# YUSynth-LFO-mainboard.net
KiCad netlist of a schematic drawn in EAGLE
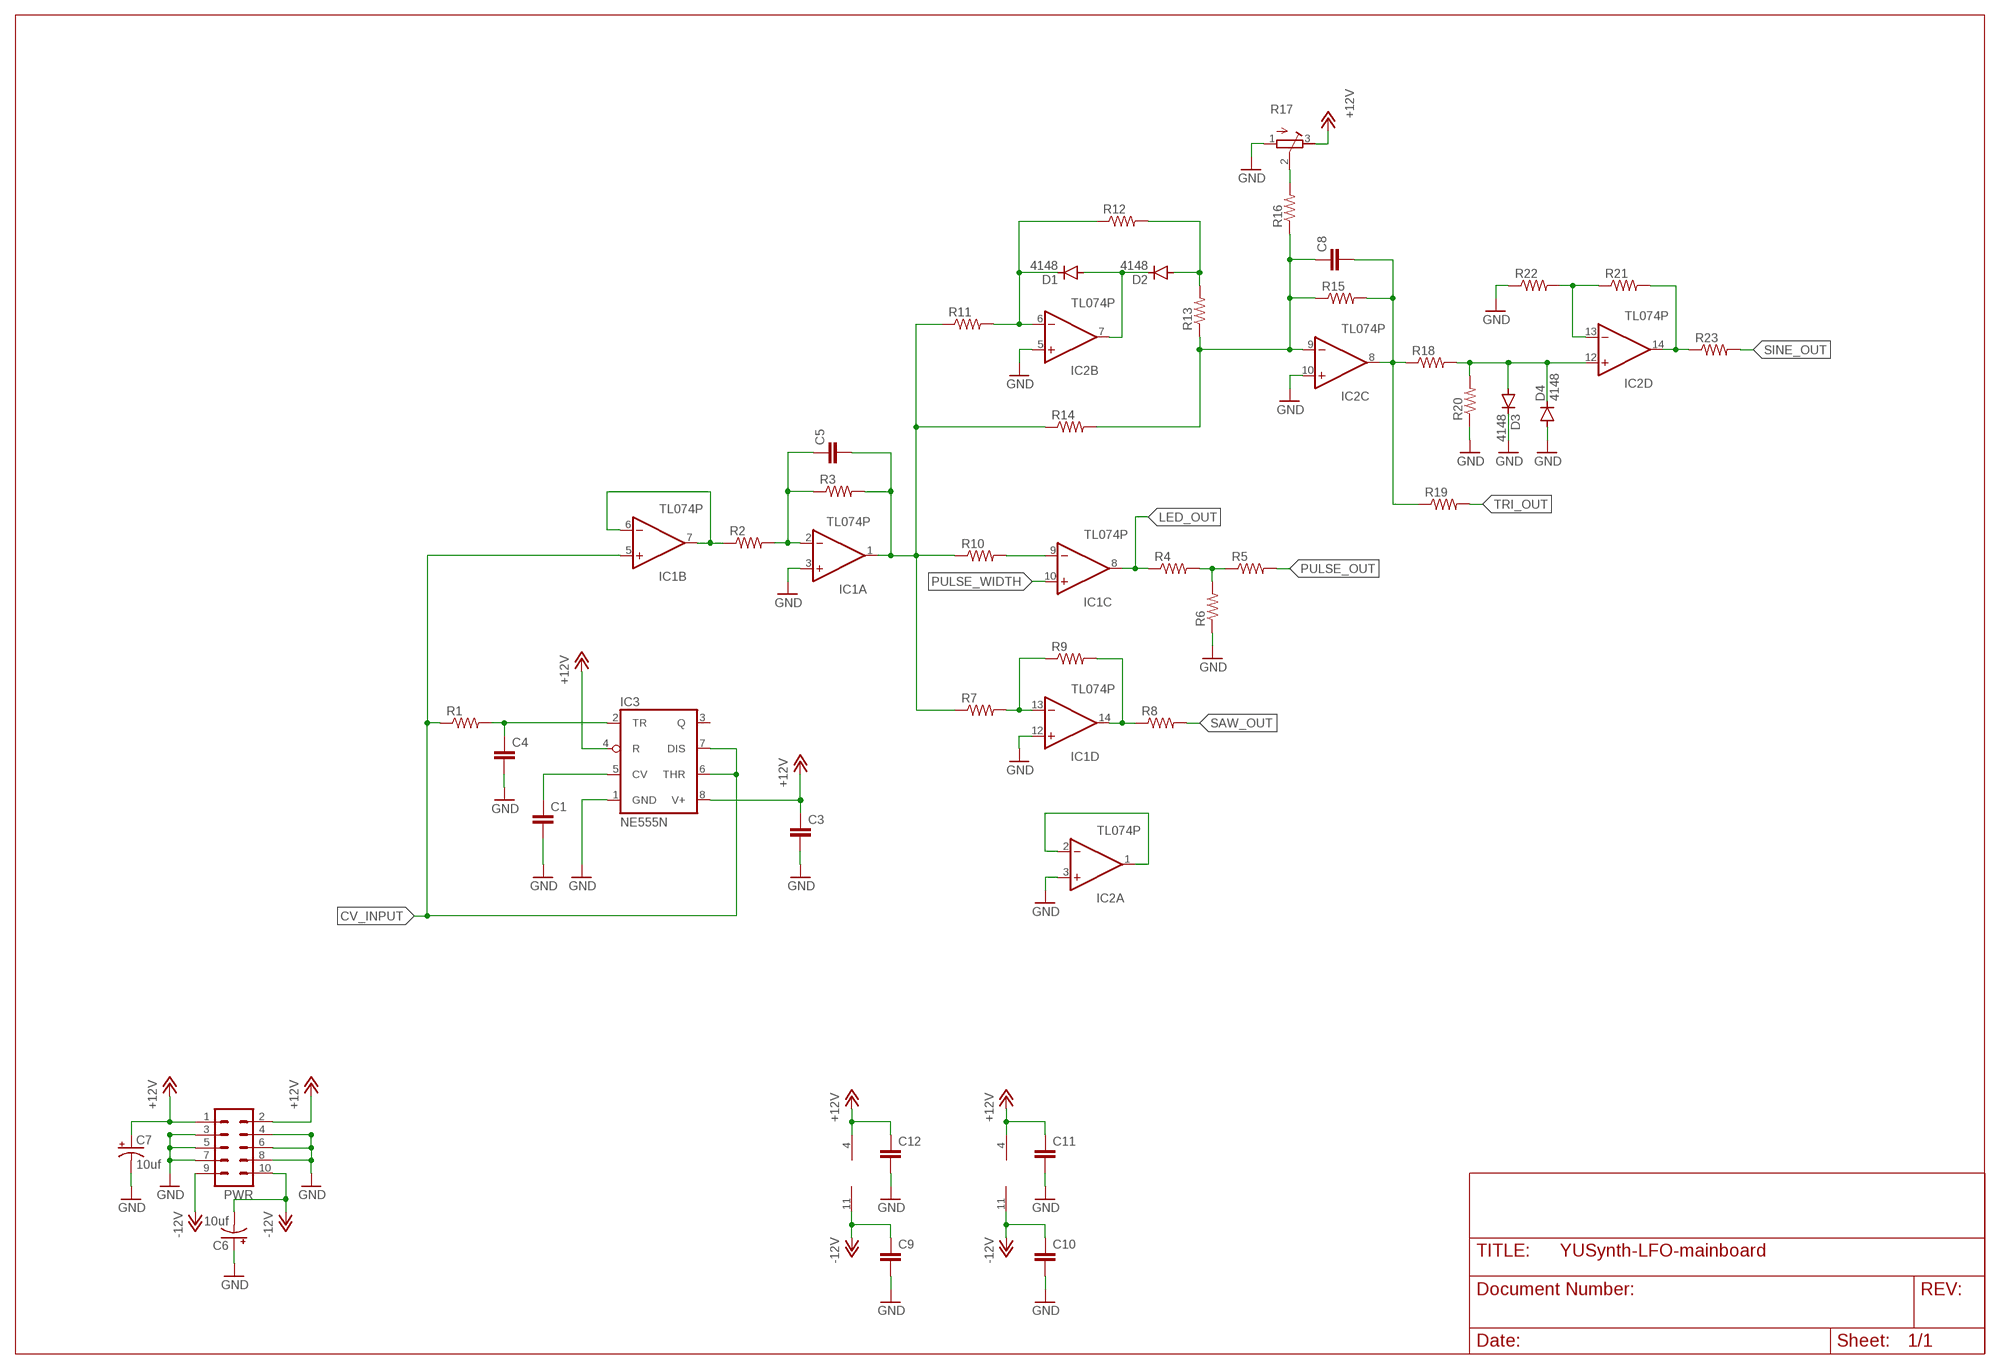
[diagram p0: schematic, sheet 1]

(export (version "E")
  (design (tool "Eeschema 10.0.6"))
  (components
    (comp (ref "C1")
      (value "C-EU050-024X044")
      (footprint "eagle-import:C050-024X044")
      (libsource (lib "eagle-import") (part "C-EU050-024X044"))
    )
    (comp (ref "C3")
      (value "C-EU050-024X044")
      (footprint "eagle-import:C050-024X044")
      (libsource (lib "eagle-import") (part "C-EU050-024X044"))
    )
    (comp (ref "C4")
      (value "C-EU050-024X044")
      (footprint "eagle-import:C050-024X044")
      (libsource (lib "eagle-import") (part "C-EU050-024X044"))
    )
    (comp (ref "C5")
      (value "C-EU050-024X044")
      (footprint "eagle-import:C050-024X044")
      (libsource (lib "eagle-import") (part "C-EU050-024X044"))
    )
    (comp (ref "C6")
      (value "10uf")
      (footprint "eagle-import:E2,5-5")
      (libsource (lib "eagle-import") (part "CPOL-USE2.5-5"))
    )
    (comp (ref "C7")
      (value "10uf")
      (footprint "eagle-import:E2,5-5")
      (libsource (lib "eagle-import") (part "CPOL-USE2.5-5"))
    )
    (comp (ref "C8")
      (value "C-EU050-024X044")
      (footprint "eagle-import:C050-024X044")
      (libsource (lib "eagle-import") (part "C-EU050-024X044"))
    )
    (comp (ref "C9")
      (value "C-EU050-024X044")
      (footprint "eagle-import:C050-024X044")
      (libsource (lib "eagle-import") (part "C-EU050-024X044"))
    )
    (comp (ref "C10")
      (value "C-EU050-024X044")
      (footprint "eagle-import:C050-024X044")
      (libsource (lib "eagle-import") (part "C-EU050-024X044"))
    )
    (comp (ref "C11")
      (value "C-EU050-024X044")
      (footprint "eagle-import:C050-024X044")
      (libsource (lib "eagle-import") (part "C-EU050-024X044"))
    )
    (comp (ref "C12")
      (value "C-EU050-024X044")
      (footprint "eagle-import:C050-024X044")
      (libsource (lib "eagle-import") (part "C-EU050-024X044"))
    )
    (comp (ref "D1")
      (value "4148")
      (footprint "eagle-import:DO35-7")
      (libsource (lib "eagle-import") (part "1N4148DO35-7"))
    )
    (comp (ref "D2")
      (value "4148")
      (footprint "eagle-import:DO35-7")
      (libsource (lib "eagle-import") (part "1N4148DO35-7"))
    )
    (comp (ref "D3")
      (value "4148")
      (footprint "eagle-import:DO35-7")
      (libsource (lib "eagle-import") (part "1N4148DO35-7"))
    )
    (comp (ref "D4")
      (value "4148")
      (footprint "eagle-import:DO35-7")
      (libsource (lib "eagle-import") (part "1N4148DO35-7"))
    )
    (comp (ref "IC1")
      (value "TL074P")
      (footprint "eagle-import:DIL14")
      (libsource (lib "eagle-import") (part "TL074P"))
    )
    (comp (ref "IC2")
      (value "TL074P")
      (footprint "eagle-import:DIL14")
      (libsource (lib "eagle-import") (part "TL074P"))
    )
    (comp (ref "IC3")
      (value "NE555N")
      (footprint "eagle-import:DIL08")
      (libsource (lib "eagle-import") (part "555NNE"))
    )
    (comp (ref "PWR")
      (value "ML10")
      (footprint "eagle-import:ML10")
      (libsource (lib "eagle-import") (part "ML10"))
    )
    (comp (ref "R1")
      (value "R-US_0207/7")
      (footprint "eagle-import:0207_7")
      (libsource (lib "eagle-import") (part "R-US_0207/7"))
    )
    (comp (ref "R2")
      (value "R-US_0207/7")
      (footprint "eagle-import:0207_7")
      (libsource (lib "eagle-import") (part "R-US_0207/7"))
    )
    (comp (ref "R3")
      (value "R-US_0207/7")
      (footprint "eagle-import:0207_7")
      (libsource (lib "eagle-import") (part "R-US_0207/7"))
    )
    (comp (ref "R4")
      (value "R-US_0207/7")
      (footprint "eagle-import:0207_7")
      (libsource (lib "eagle-import") (part "R-US_0207/7"))
    )
    (comp (ref "R5")
      (value "R-US_0207/7")
      (footprint "eagle-import:0207_7")
      (libsource (lib "eagle-import") (part "R-US_0207/7"))
    )
    (comp (ref "R6")
      (value "R-US_0207/7")
      (footprint "eagle-import:0207_7")
      (libsource (lib "eagle-import") (part "R-US_0207/7"))
    )
    (comp (ref "R7")
      (value "R-US_0207/7")
      (footprint "eagle-import:0207_7")
      (libsource (lib "eagle-import") (part "R-US_0207/7"))
    )
    (comp (ref "R8")
      (value "R-US_0207/7")
      (footprint "eagle-import:0207_7")
      (libsource (lib "eagle-import") (part "R-US_0207/7"))
    )
    (comp (ref "R9")
      (value "R-US_0207/7")
      (footprint "eagle-import:0207_7")
      (libsource (lib "eagle-import") (part "R-US_0207/7"))
    )
    (comp (ref "R10")
      (value "R-US_0207/7")
      (footprint "eagle-import:0207_7")
      (libsource (lib "eagle-import") (part "R-US_0207/7"))
    )
    (comp (ref "R11")
      (value "R-US_0207/7")
      (footprint "eagle-import:0207_7")
      (libsource (lib "eagle-import") (part "R-US_0207/7"))
    )
    (comp (ref "R12")
      (value "R-US_0207/7")
      (footprint "eagle-import:0207_7")
      (libsource (lib "eagle-import") (part "R-US_0207/7"))
    )
    (comp (ref "R13")
      (value "R-US_0207/7")
      (footprint "eagle-import:0207_7")
      (libsource (lib "eagle-import") (part "R-US_0207/7"))
    )
    (comp (ref "R14")
      (value "R-US_0207/7")
      (footprint "eagle-import:0207_7")
      (libsource (lib "eagle-import") (part "R-US_0207/7"))
    )
    (comp (ref "R15")
      (value "R-US_0207/7")
      (footprint "eagle-import:0207_7")
      (libsource (lib "eagle-import") (part "R-US_0207/7"))
    )
    (comp (ref "R16")
      (value "R-US_0207/7")
      (footprint "eagle-import:0207_7")
      (libsource (lib "eagle-import") (part "R-US_0207/7"))
    )
    (comp (ref "R17")
      (value "R-TRIMM64W")
      (footprint "eagle-import:RTRIM64W")
      (libsource (lib "eagle-import") (part "R-TRIMM64W"))
    )
    (comp (ref "R18")
      (value "R-US_0207/7")
      (footprint "eagle-import:0207_7")
      (libsource (lib "eagle-import") (part "R-US_0207/7"))
    )
    (comp (ref "R19")
      (value "R-US_0207/7")
      (footprint "eagle-import:0207_7")
      (libsource (lib "eagle-import") (part "R-US_0207/7"))
    )
    (comp (ref "R20")
      (value "R-US_0207/7")
      (footprint "eagle-import:0207_7")
      (libsource (lib "eagle-import") (part "R-US_0207/7"))
    )
    (comp (ref "R21")
      (value "R-US_0207/7")
      (footprint "eagle-import:0207_7")
      (libsource (lib "eagle-import") (part "R-US_0207/7"))
    )
    (comp (ref "R22")
      (value "R-US_0207/7")
      (footprint "eagle-import:0207_7")
      (libsource (lib "eagle-import") (part "R-US_0207/7"))
    )
    (comp (ref "R23")
      (value "R-US_0207/7")
      (footprint "eagle-import:0207_7")
      (libsource (lib "eagle-import") (part "R-US_0207/7"))
    )
  )
  (nets
    (net (code "1") (name "+12V") (class "Default")
      (node (ref "C11") (pin "1") (pinfunction "1_1") (pintype "passive"))
      (node (ref "C12") (pin "1") (pinfunction "1_1") (pintype "passive"))
      (node (ref "C3") (pin "1") (pinfunction "1_1") (pintype "passive"))
      (node (ref "C7") (pin "+") (pinfunction "+_+") (pintype "passive"))
      (node (ref "IC1") (pin "4") (pinfunction "V+_4") (pintype "power_in"))
      (node (ref "IC2") (pin "4") (pinfunction "V+_4") (pintype "power_in"))
      (node (ref "IC3") (pin "4") (pinfunction "R_4") (pintype "input"))
      (node (ref "IC3") (pin "8") (pinfunction "V+_8") (pintype "power_in"))
      (node (ref "PWR") (pin "1") (pinfunction "1_1") (pintype "passive"))
      (node (ref "PWR") (pin "2") (pinfunction "2_2") (pintype "passive"))
      (node (ref "R17") (pin "3") (pinfunction "E_3") (pintype "passive"))
    )
    (net (code "2") (name "-12V") (class "Default")
      (node (ref "C10") (pin "1") (pinfunction "1_1") (pintype "passive"))
      (node (ref "C6") (pin "-") (pinfunction "-_-") (pintype "passive"))
      (node (ref "C9") (pin "1") (pinfunction "1_1") (pintype "passive"))
      (node (ref "IC1") (pin "11") (pinfunction "V-_11") (pintype "power_in"))
      (node (ref "IC2") (pin "11") (pinfunction "V-_11") (pintype "power_in"))
      (node (ref "PWR") (pin "10") (pinfunction "10_10") (pintype "passive"))
      (node (ref "PWR") (pin "9") (pinfunction "9_9") (pintype "passive"))
    )
    (net (code "3") (name "CV_INPUT") (class "Default")
      (node (ref "IC1") (pin "5") (pinfunction "+IN_5") (pintype "input"))
      (node (ref "IC3") (pin "6") (pinfunction "THR_6") (pintype "input"))
      (node (ref "IC3") (pin "7") (pinfunction "DIS_7") (pintype "input"))
      (node (ref "R1") (pin "1") (pinfunction "1_1") (pintype "passive"))
    )
    (net (code "4") (name "GND") (class "Default")
      (node (ref "C1") (pin "2") (pinfunction "2_2") (pintype "passive"))
      (node (ref "C10") (pin "2") (pinfunction "2_2") (pintype "passive"))
      (node (ref "C11") (pin "2") (pinfunction "2_2") (pintype "passive"))
      (node (ref "C12") (pin "2") (pinfunction "2_2") (pintype "passive"))
      (node (ref "C3") (pin "2") (pinfunction "2_2") (pintype "passive"))
      (node (ref "C4") (pin "2") (pinfunction "2_2") (pintype "passive"))
      (node (ref "C6") (pin "+") (pinfunction "+_+") (pintype "passive"))
      (node (ref "C7") (pin "-") (pinfunction "-_-") (pintype "passive"))
      (node (ref "C9") (pin "2") (pinfunction "2_2") (pintype "passive"))
      (node (ref "D3") (pin "C") (pinfunction "C_C") (pintype "passive"))
      (node (ref "D4") (pin "A") (pinfunction "A_A") (pintype "passive"))
      (node (ref "IC1") (pin "12") (pinfunction "+IN_12") (pintype "input"))
      (node (ref "IC1") (pin "3") (pinfunction "+IN_3") (pintype "input"))
      (node (ref "IC2") (pin "10") (pinfunction "+IN_10") (pintype "input"))
      (node (ref "IC2") (pin "3") (pinfunction "+IN_3") (pintype "input"))
      (node (ref "IC2") (pin "5") (pinfunction "+IN_5") (pintype "input"))
      (node (ref "IC3") (pin "1") (pinfunction "GND_1") (pintype "power_in"))
      (node (ref "PWR") (pin "3") (pinfunction "3_3") (pintype "passive"))
      (node (ref "PWR") (pin "4") (pinfunction "4_4") (pintype "passive"))
      (node (ref "PWR") (pin "5") (pinfunction "5_5") (pintype "passive"))
      (node (ref "PWR") (pin "6") (pinfunction "6_6") (pintype "passive"))
      (node (ref "PWR") (pin "7") (pinfunction "7_7") (pintype "passive"))
      (node (ref "PWR") (pin "8") (pinfunction "8_8") (pintype "passive"))
      (node (ref "R17") (pin "1") (pinfunction "A_1") (pintype "passive"))
      (node (ref "R20") (pin "1") (pinfunction "1_1") (pintype "passive"))
      (node (ref "R22") (pin "1") (pinfunction "1_1") (pintype "passive"))
      (node (ref "R6") (pin "1") (pinfunction "1_1") (pintype "passive"))
    )
    (net (code "5") (name "LED_OUT") (class "Default")
      (node (ref "IC1") (pin "8") (pinfunction "OUT_8") (pintype "output"))
      (node (ref "R4") (pin "1") (pinfunction "1_1") (pintype "passive"))
    )
    (net (code "6") (name "Net-(D2-PadA)") (class "Default")
      (node (ref "D2") (pin "A") (pinfunction "A_A") (pintype "passive"))
      (node (ref "R12") (pin "2") (pinfunction "2_2") (pintype "passive"))
      (node (ref "R13") (pin "2") (pinfunction "2_2") (pintype "passive"))
    )
    (net (code "7") (name "Net-(IC1A--IN)") (class "Default")
      (node (ref "C5") (pin "1") (pinfunction "1_1") (pintype "passive"))
      (node (ref "IC1") (pin "2") (pinfunction "-IN_2") (pintype "input"))
      (node (ref "R2") (pin "2") (pinfunction "2_2") (pintype "passive"))
      (node (ref "R3") (pin "1") (pinfunction "1_1") (pintype "passive"))
    )
    (net (code "8") (name "Net-(IC1A-OUT)") (class "Default")
      (node (ref "C5") (pin "2") (pinfunction "2_2") (pintype "passive"))
      (node (ref "IC1") (pin "1") (pinfunction "OUT_1") (pintype "output"))
      (node (ref "R10") (pin "1") (pinfunction "1_1") (pintype "passive"))
      (node (ref "R11") (pin "1") (pinfunction "1_1") (pintype "passive"))
      (node (ref "R14") (pin "1") (pinfunction "1_1") (pintype "passive"))
      (node (ref "R3") (pin "2") (pinfunction "2_2") (pintype "passive"))
      (node (ref "R7") (pin "1") (pinfunction "1_1") (pintype "passive"))
    )
    (net (code "9") (name "Net-(IC1B--IN)") (class "Default")
      (node (ref "IC1") (pin "6") (pinfunction "-IN_6") (pintype "input"))
      (node (ref "IC1") (pin "7") (pinfunction "OUT_7") (pintype "output"))
      (node (ref "R2") (pin "1") (pinfunction "1_1") (pintype "passive"))
    )
    (net (code "10") (name "Net-(IC1C--IN)") (class "Default")
      (node (ref "IC1") (pin "9") (pinfunction "-IN_9") (pintype "input"))
      (node (ref "R10") (pin "2") (pinfunction "2_2") (pintype "passive"))
    )
    (net (code "11") (name "Net-(IC1D--IN)") (class "Default")
      (node (ref "IC1") (pin "13") (pinfunction "-IN_13") (pintype "input"))
      (node (ref "R7") (pin "2") (pinfunction "2_2") (pintype "passive"))
      (node (ref "R9") (pin "1") (pinfunction "1_1") (pintype "passive"))
    )
    (net (code "12") (name "Net-(IC1D-OUT)") (class "Default")
      (node (ref "IC1") (pin "14") (pinfunction "OUT_14") (pintype "output"))
      (node (ref "R8") (pin "1") (pinfunction "1_1") (pintype "passive"))
      (node (ref "R9") (pin "2") (pinfunction "2_2") (pintype "passive"))
    )
    (net (code "13") (name "Net-(IC2A--IN)") (class "Default")
      (node (ref "IC2") (pin "1") (pinfunction "OUT_1") (pintype "output"))
      (node (ref "IC2") (pin "2") (pinfunction "-IN_2") (pintype "input"))
    )
    (net (code "14") (name "Net-(IC2B--IN)") (class "Default")
      (node (ref "D1") (pin "C") (pinfunction "C_C") (pintype "passive"))
      (node (ref "IC2") (pin "6") (pinfunction "-IN_6") (pintype "input"))
      (node (ref "R11") (pin "2") (pinfunction "2_2") (pintype "passive"))
      (node (ref "R12") (pin "1") (pinfunction "1_1") (pintype "passive"))
    )
    (net (code "15") (name "Net-(IC2B-OUT)") (class "Default")
      (node (ref "D1") (pin "A") (pinfunction "A_A") (pintype "passive"))
      (node (ref "D2") (pin "C") (pinfunction "C_C") (pintype "passive"))
      (node (ref "IC2") (pin "7") (pinfunction "OUT_7") (pintype "output"))
    )
    (net (code "16") (name "Net-(IC2C--IN)") (class "Default")
      (node (ref "C8") (pin "1") (pinfunction "1_1") (pintype "passive"))
      (node (ref "IC2") (pin "9") (pinfunction "-IN_9") (pintype "input"))
      (node (ref "R13") (pin "1") (pinfunction "1_1") (pintype "passive"))
      (node (ref "R14") (pin "2") (pinfunction "2_2") (pintype "passive"))
      (node (ref "R15") (pin "1") (pinfunction "1_1") (pintype "passive"))
      (node (ref "R16") (pin "1") (pinfunction "1_1") (pintype "passive"))
    )
    (net (code "17") (name "Net-(IC2C-OUT)") (class "Default")
      (node (ref "C8") (pin "2") (pinfunction "2_2") (pintype "passive"))
      (node (ref "IC2") (pin "8") (pinfunction "OUT_8") (pintype "output"))
      (node (ref "R15") (pin "2") (pinfunction "2_2") (pintype "passive"))
      (node (ref "R18") (pin "1") (pinfunction "1_1") (pintype "passive"))
      (node (ref "R19") (pin "1") (pinfunction "1_1") (pintype "passive"))
    )
    (net (code "18") (name "Net-(IC2D-+IN)") (class "Default")
      (node (ref "D3") (pin "A") (pinfunction "A_A") (pintype "passive"))
      (node (ref "D4") (pin "C") (pinfunction "C_C") (pintype "passive"))
      (node (ref "IC2") (pin "12") (pinfunction "+IN_12") (pintype "input"))
      (node (ref "R18") (pin "2") (pinfunction "2_2") (pintype "passive"))
      (node (ref "R20") (pin "2") (pinfunction "2_2") (pintype "passive"))
    )
    (net (code "19") (name "Net-(IC2D--IN)") (class "Default")
      (node (ref "IC2") (pin "13") (pinfunction "-IN_13") (pintype "input"))
      (node (ref "R21") (pin "1") (pinfunction "1_1") (pintype "passive"))
      (node (ref "R22") (pin "2") (pinfunction "2_2") (pintype "passive"))
    )
    (net (code "20") (name "Net-(IC2D-OUT)") (class "Default")
      (node (ref "IC2") (pin "14") (pinfunction "OUT_14") (pintype "output"))
      (node (ref "R21") (pin "2") (pinfunction "2_2") (pintype "passive"))
      (node (ref "R23") (pin "1") (pinfunction "1_1") (pintype "passive"))
    )
    (net (code "21") (name "Net-(IC3-CV)") (class "Default")
      (node (ref "C1") (pin "1") (pinfunction "1_1") (pintype "passive"))
      (node (ref "IC3") (pin "5") (pinfunction "CV_5") (pintype "input"))
    )
    (net (code "22") (name "Net-(IC3-TR)") (class "Default")
      (node (ref "C4") (pin "1") (pinfunction "1_1") (pintype "passive"))
      (node (ref "IC3") (pin "2") (pinfunction "TR_2") (pintype "input"))
      (node (ref "R1") (pin "2") (pinfunction "2_2") (pintype "passive"))
    )
    (net (code "23") (name "Net-(R4-Pad2)") (class "Default")
      (node (ref "R4") (pin "2") (pinfunction "2_2") (pintype "passive"))
      (node (ref "R5") (pin "1") (pinfunction "1_1") (pintype "passive"))
      (node (ref "R6") (pin "2") (pinfunction "2_2") (pintype "passive"))
    )
    (net (code "24") (name "Net-(R17-S)") (class "Default")
      (node (ref "R16") (pin "2") (pinfunction "2_2") (pintype "passive"))
      (node (ref "R17") (pin "2") (pinfunction "S_2") (pintype "passive"))
    )
    (net (code "25") (name "PULSE_OUT") (class "Default")
      (node (ref "R5") (pin "2") (pinfunction "2_2") (pintype "passive"))
    )
    (net (code "26") (name "PULSE_WIDTH") (class "Default")
      (node (ref "IC1") (pin "10") (pinfunction "+IN_10") (pintype "input"))
    )
    (net (code "27") (name "SAW_OUT") (class "Default")
      (node (ref "R8") (pin "2") (pinfunction "2_2") (pintype "passive"))
    )
    (net (code "28") (name "SINE_OUT") (class "Default")
      (node (ref "R23") (pin "2") (pinfunction "2_2") (pintype "passive"))
    )
    (net (code "29") (name "TRI_OUT") (class "Default")
      (node (ref "R19") (pin "2") (pinfunction "2_2") (pintype "passive"))
    )
    (net (code "30") (name "unconnected-(IC3-Q-Pad3)") (class "Default")
      (node (ref "IC3") (pin "3") (pinfunction "Q_3") (pintype "output"))
    )
  )
)
